# mykeyboard.net
KiCad netlist of a schematic drawn in EasyEDA Pro
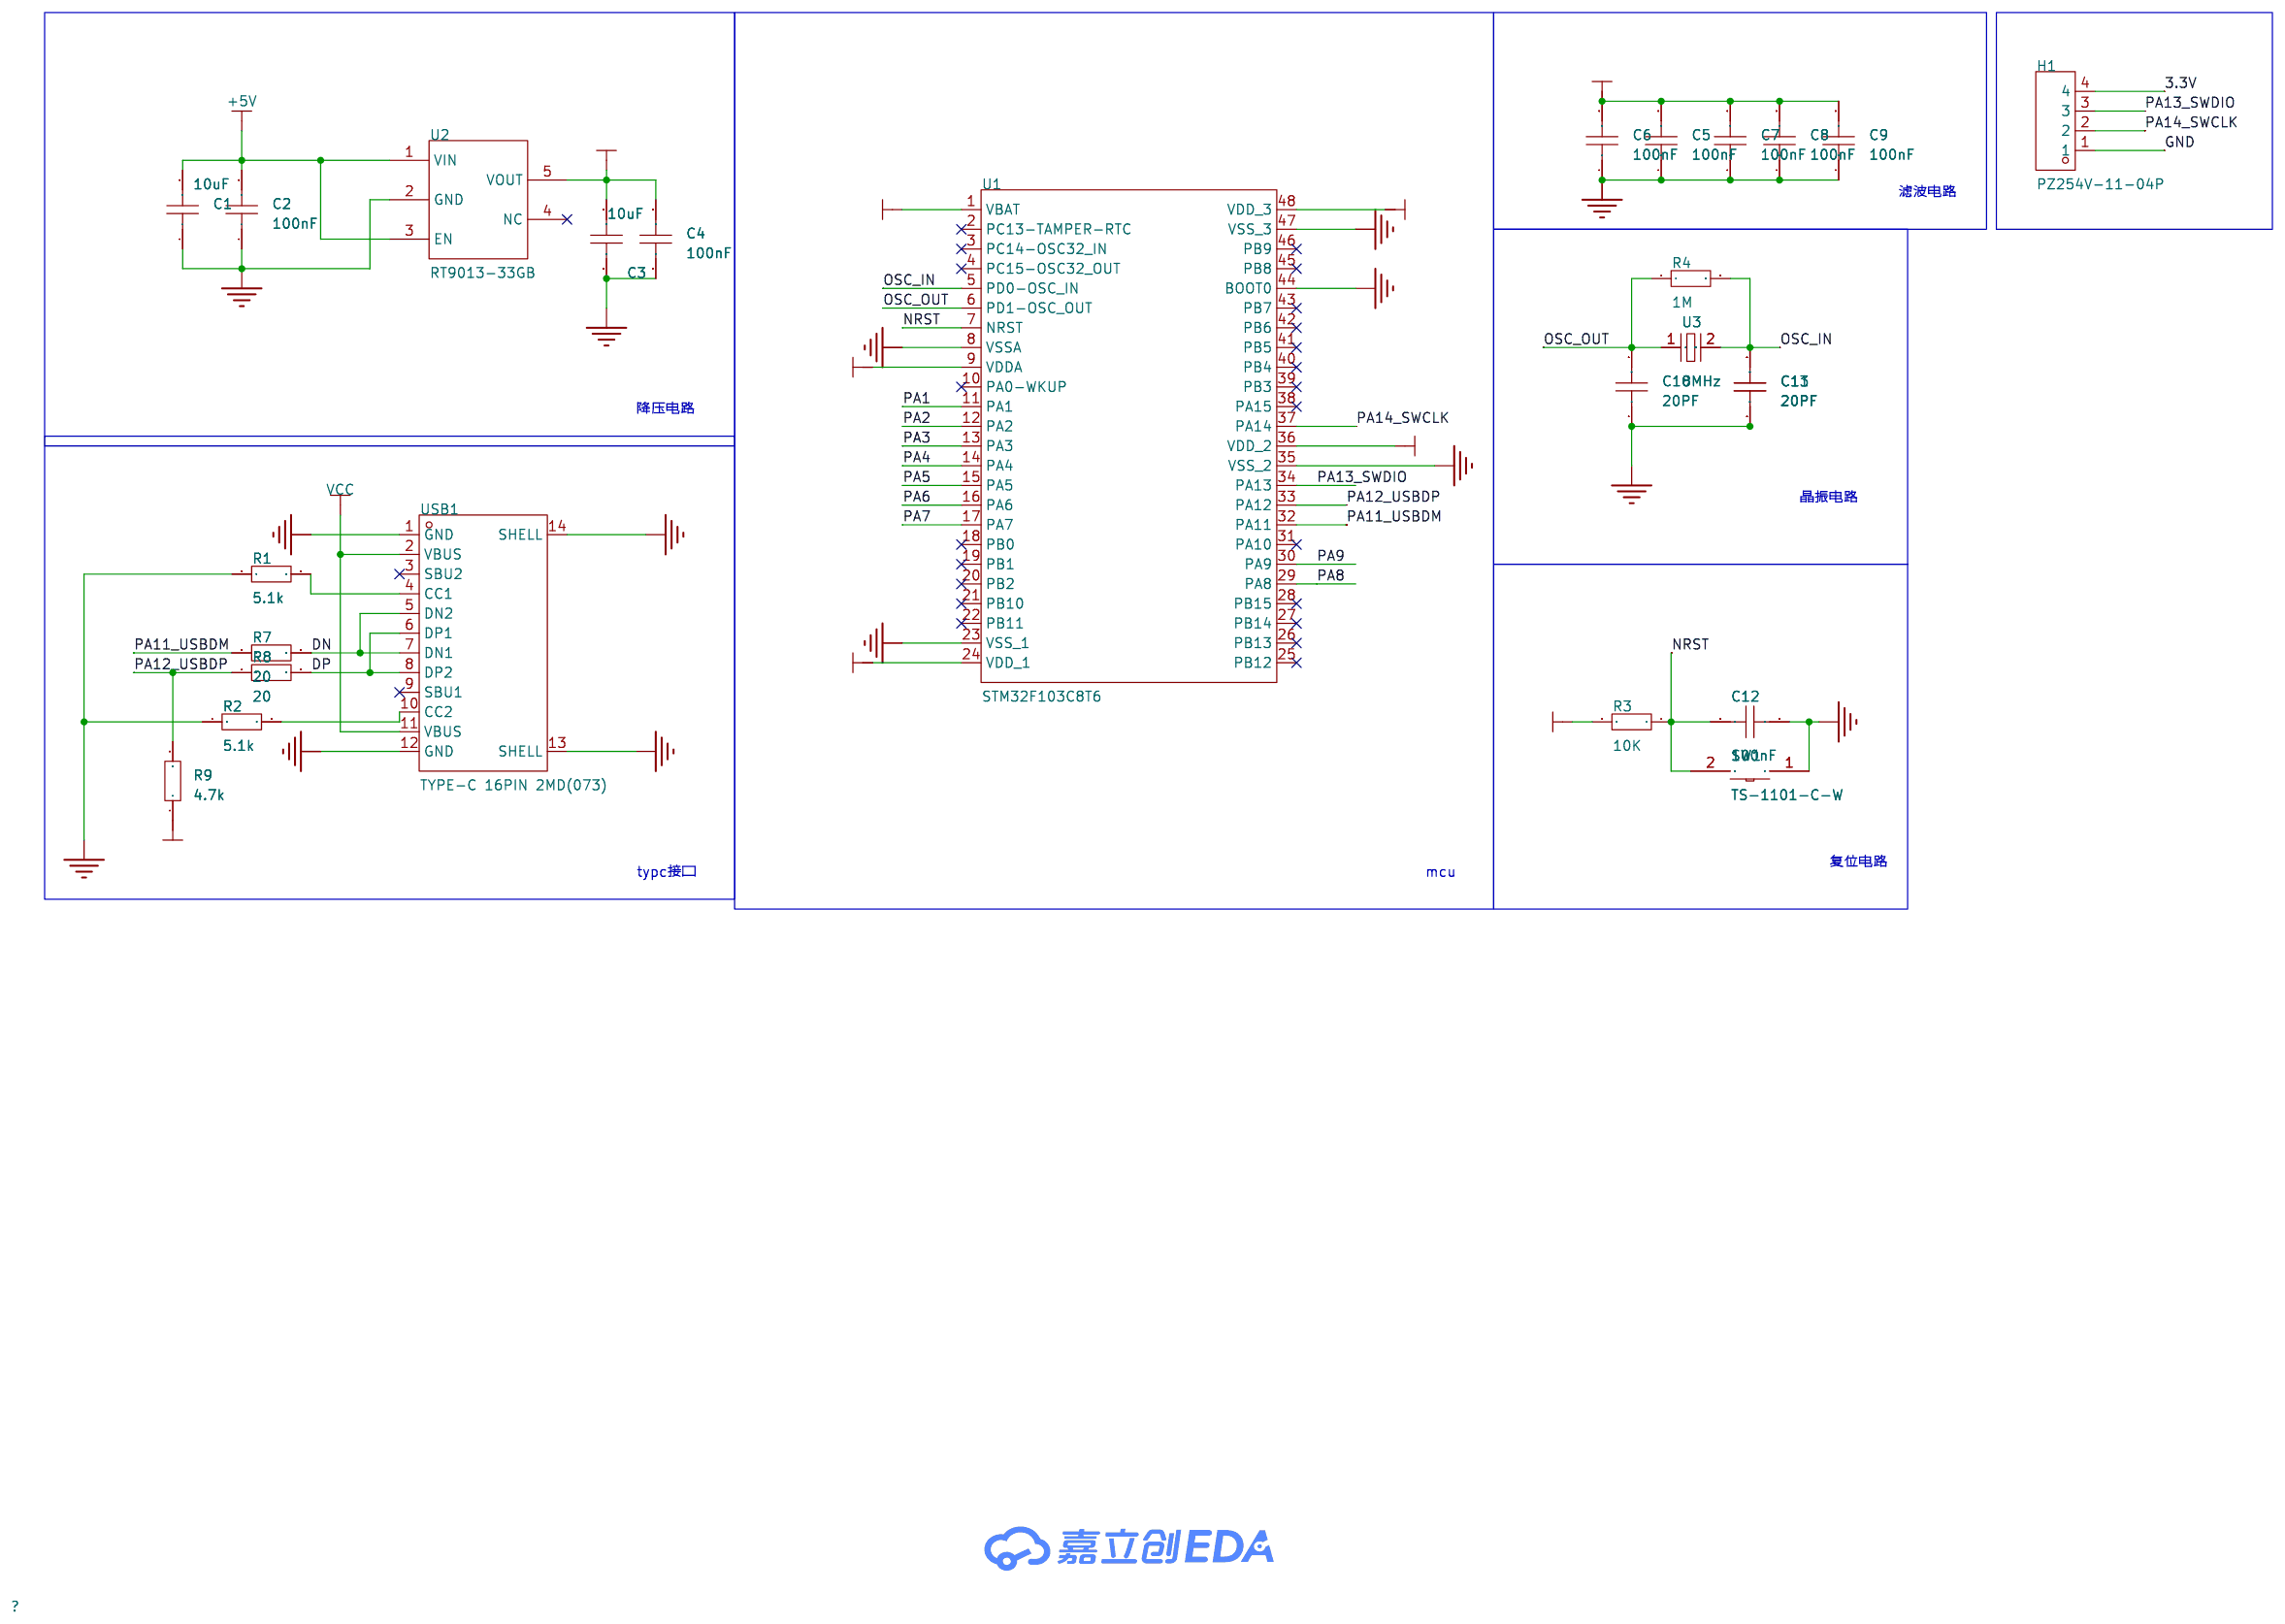
[diagram p0: P1]
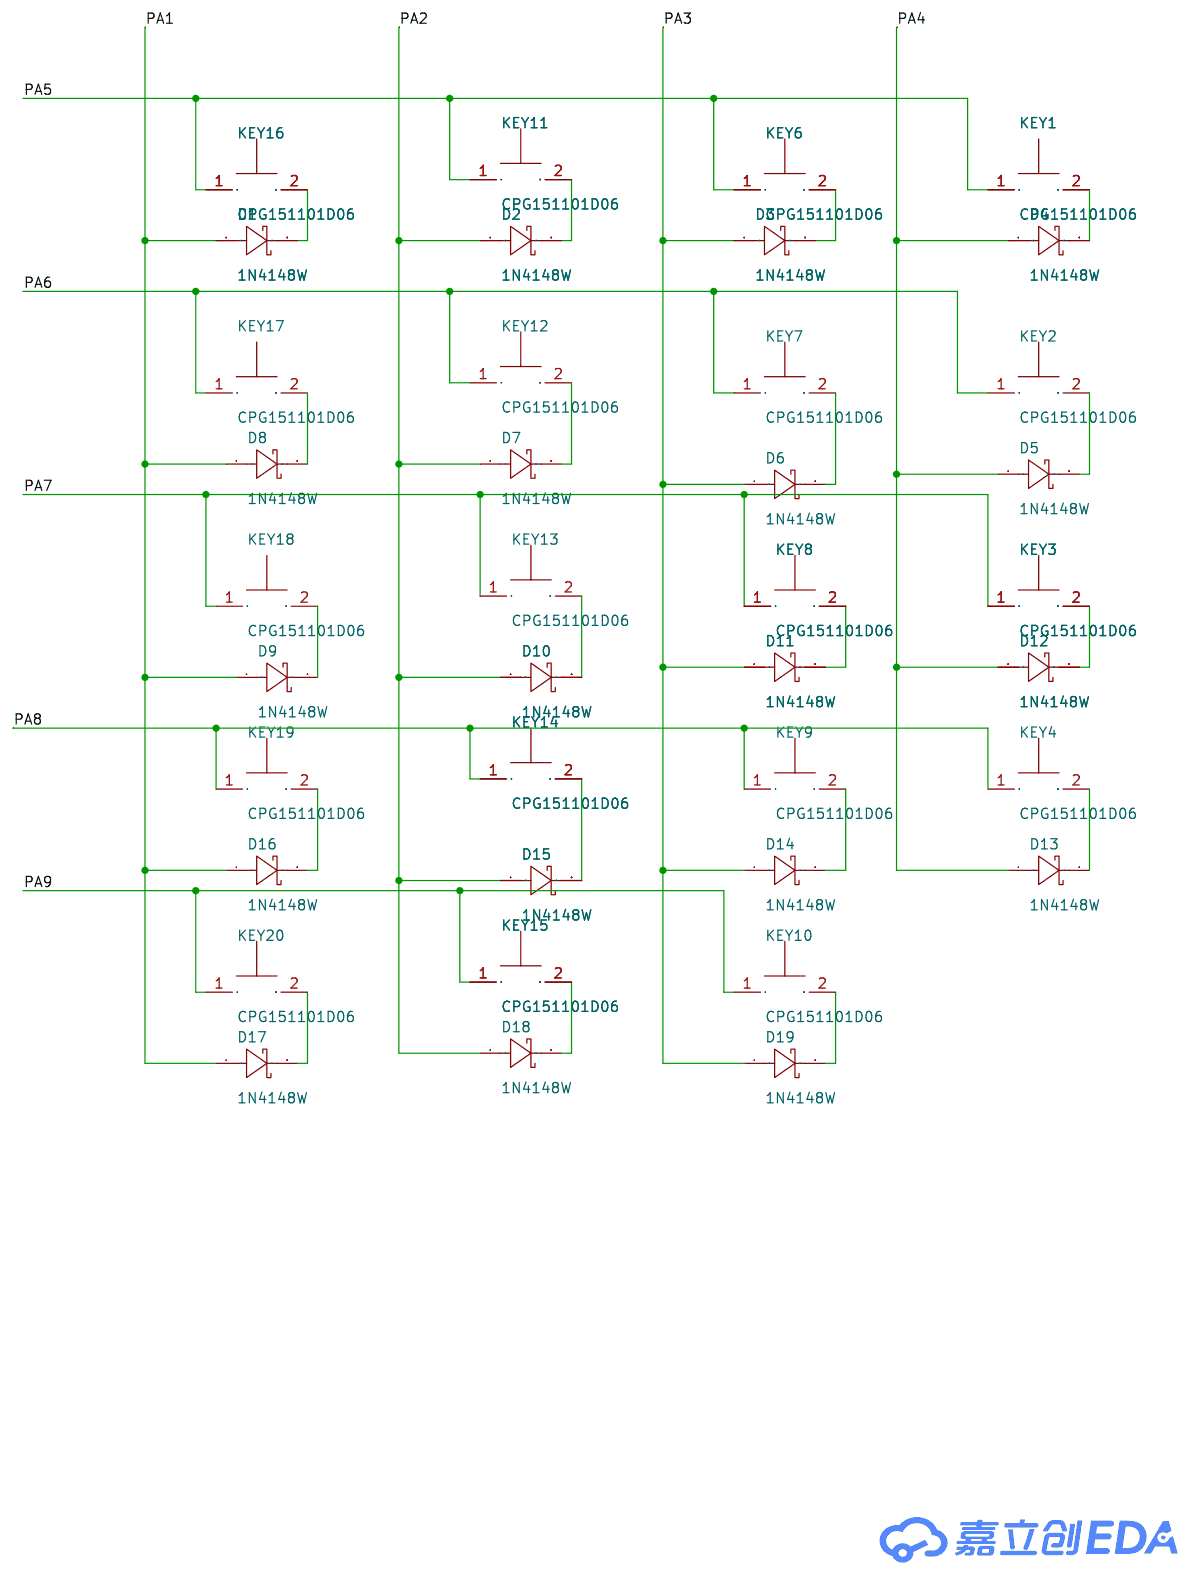
[diagram p1: P2]

(export (version "E")
  (design (tool "Eeschema 10.0.6"))
  (components
    (comp (ref "C1")
      (value "10uF")
      (footprint "easyedapro:C0603")
      (libsource (lib "easyedapro") (part "Capacitance"))
    )
    (comp (ref "C2")
      (value "100nF")
      (footprint "easyedapro:C0603")
      (libsource (lib "easyedapro") (part "Capacitance"))
    )
    (comp (ref "C3")
      (value "10uF")
      (footprint "easyedapro:C0603")
      (libsource (lib "easyedapro") (part "Capacitance"))
    )
    (comp (ref "C4")
      (value "100nF")
      (footprint "easyedapro:C0603")
      (libsource (lib "easyedapro") (part "Capacitance"))
    )
    (comp (ref "C5")
      (value "100nF")
      (footprint "easyedapro:C0603")
      (libsource (lib "easyedapro") (part "Capacitance"))
    )
    (comp (ref "C6")
      (value "100nF")
      (footprint "easyedapro:C0603")
      (libsource (lib "easyedapro") (part "Capacitance"))
    )
    (comp (ref "C7")
      (value "100nF")
      (footprint "easyedapro:C0603")
      (libsource (lib "easyedapro") (part "Capacitance"))
    )
    (comp (ref "C8")
      (value "100nF")
      (footprint "easyedapro:C0603")
      (libsource (lib "easyedapro") (part "Capacitance"))
    )
    (comp (ref "C9")
      (value "100nF")
      (footprint "easyedapro:C0603")
      (libsource (lib "easyedapro") (part "Capacitance"))
    )
    (comp (ref "C10")
      (value "20PF")
      (footprint "easyedapro:C0603")
      (libsource (lib "easyedapro") (part "Capacitance"))
    )
    (comp (ref "C11")
      (value "20PF")
      (footprint "easyedapro:C0603")
      (libsource (lib "easyedapro") (part "Capacitance"))
    )
    (comp (ref "C12")
      (value "100nF")
      (footprint "easyedapro:C0603")
      (libsource (lib "easyedapro") (part "Capacitance"))
    )
    (comp (ref "C13")
      (value "20PF")
      (footprint "easyedapro:C0603")
      (libsource (lib "easyedapro") (part "Capacitance"))
    )
    (comp (ref "H1")
      (value "PZ254V-11-04P")
      (footprint "easyedapro:HDR-TH_4P-P2.54-V-M")
      (fields (field (name "Manufacturer") "XFCN(兴飞)"))
      (libsource (lib "easyedapro") (part "PZ254V-11-04P_C2691448"))
    )
    (comp (ref "R1") (value "5.1k") (footprint "easyedapro:R0603") (libsource (lib "easyedapro") (part "电阻")))
    (comp (ref "R2") (value "5.1k") (footprint "easyedapro:R0603") (libsource (lib "easyedapro") (part "电阻")))
    (comp (ref "R3") (value "10K") (footprint "easyedapro:R0603") (libsource (lib "easyedapro") (part "电阻")))
    (comp (ref "R4") (value "1M") (footprint "easyedapro:R0603") (libsource (lib "easyedapro") (part "电阻")))
    (comp (ref "R7") (value "20") (footprint "easyedapro:R0603") (libsource (lib "easyedapro") (part "电阻")))
    (comp (ref "R8") (value "20") (footprint "easyedapro:R0603") (libsource (lib "easyedapro") (part "电阻")))
    (comp (ref "R9") (value "4.7k") (footprint "easyedapro:R0603") (libsource (lib "easyedapro") (part "电阻")))
    (comp (ref "SW1")
      (value "TS-1101-C-W")
      (footprint "easyedapro:SW-SMD_L6.0-W3.3-LS8.0")
      (fields (field (name "Manufacturer") "XKB Connectivity(中国星坤)"))
      (libsource (lib "easyedapro") (part "TS-1101-C-W"))
    )
    (comp (ref "U1")
      (value "STM32F103C8T6")
      (footprint "easyedapro:LQFP-48_L7.0-W7.0-P0.50-LS9.0-BL")
      (description "CPU内核:ARM-M3;CPU最大主频:72MHz;应用领域:-;")
      (fields (field (name "Manufacturer") "ST(意法半导体)"))
      (libsource (lib "easyedapro") (part "STM32F103C8T6"))
    )
    (comp (ref "U2")
      (value "RT9013-33GB")
      (footprint "easyedapro:SOT-23-5_L3.0-W1.7-P0.95-LS2.8-BL")
      (description "输出类型:固定;工作电压:5.5V;输出电压:3.3V;输出电流:500mA;电源纹波抑制比(PSRR):50dB@(10kHz);输出极性:正极;")
      (fields (field (name "Manufacturer") "RICHTEK(立锜)"))
      (libsource (lib "easyedapro") (part "RT9013-33GB"))
    )
    (comp (ref "U3")
      (value "8MHz")
      (footprint "easyedapro:HC-49S_L7.0-W4.0")
      (description "频率:8MHz;常温频差:±20ppm;负载电容:20pF;频率稳定度:±30ppm;")
      (fields (field (name "Manufacturer Part") "8M 20PF 20PPM") (field (name "Manufacturer") "SOSET(索斯特)"))
      (libsource (lib "easyedapro") (part "8M 20PF 20PPM"))
    )
    (comp (ref "USB1")
      (value "TYPE-C 16PIN 2MD(073)")
      (footprint "easyedapro:USB-C-SMD_TYPE-C-6PIN-2MD-073")
      (description "连接器类型:Type-C;协议标准:-;公母:母;安装方式:卧贴;触点数量:16P;端口数量:1;额定电流 - 电源:3A;工作温度:-25°C~+85°C;")
      (fields (field (name "Manufacturer") "SHOU HAN(首韩)"))
      (libsource (lib "easyedapro") (part "TYPE-C 16PIN 2MD(073)"))
    )
    (comp (ref "D1")
      (value "1N4148W")
      (footprint "easyedapro:SOD-123_L2.7-W1.6-LS3.7-FD")
      (description "二极管配置:独立式;正向压降(Vf):1.25V@150mA;直流反向耐压(Vr):100V;整流电流:150mA;反向恢复时间(Trr):4ns;")
      (fields (field (name "Manufacturer") "R+O(宏嘉诚)"))
      (libsource (lib "easyedapro") (part "1N4148W_C7420318"))
    )
    (comp (ref "D2")
      (value "1N4148W")
      (footprint "easyedapro:SOD-123_L2.7-W1.6-LS3.7-FD")
      (description "二极管配置:独立式;正向压降(Vf):1.25V@150mA;直流反向耐压(Vr):100V;整流电流:150mA;反向恢复时间(Trr):4ns;")
      (fields (field (name "Manufacturer") "R+O(宏嘉诚)"))
      (libsource (lib "easyedapro") (part "1N4148W_C7420318"))
    )
    (comp (ref "D3")
      (value "1N4148W")
      (footprint "easyedapro:SOD-123_L2.7-W1.6-LS3.7-FD")
      (description "二极管配置:独立式;正向压降(Vf):1.25V@150mA;直流反向耐压(Vr):100V;整流电流:150mA;反向恢复时间(Trr):4ns;")
      (fields (field (name "Manufacturer") "R+O(宏嘉诚)"))
      (libsource (lib "easyedapro") (part "1N4148W_C7420318"))
    )
    (comp (ref "D4")
      (value "1N4148W")
      (footprint "easyedapro:SOD-123_L2.7-W1.6-LS3.7-FD")
      (description "二极管配置:独立式;正向压降(Vf):1.25V@150mA;直流反向耐压(Vr):100V;整流电流:150mA;反向恢复时间(Trr):4ns;")
      (fields (field (name "Manufacturer") "R+O(宏嘉诚)"))
      (libsource (lib "easyedapro") (part "1N4148W_C7420318"))
    )
    (comp (ref "D5")
      (value "1N4148W")
      (footprint "easyedapro:SOD-123_L2.7-W1.6-LS3.7-FD")
      (description "二极管配置:独立式;正向压降(Vf):1.25V@150mA;直流反向耐压(Vr):100V;整流电流:150mA;反向恢复时间(Trr):4ns;")
      (fields (field (name "Manufacturer") "R+O(宏嘉诚)"))
      (libsource (lib "easyedapro") (part "1N4148W_C7420318"))
    )
    (comp (ref "D6")
      (value "1N4148W")
      (footprint "easyedapro:SOD-123_L2.7-W1.6-LS3.7-FD")
      (description "二极管配置:独立式;正向压降(Vf):1.25V@150mA;直流反向耐压(Vr):100V;整流电流:150mA;反向恢复时间(Trr):4ns;")
      (fields (field (name "Manufacturer") "R+O(宏嘉诚)"))
      (libsource (lib "easyedapro") (part "1N4148W_C7420318"))
    )
    (comp (ref "D7")
      (value "1N4148W")
      (footprint "easyedapro:SOD-123_L2.7-W1.6-LS3.7-FD")
      (description "二极管配置:独立式;正向压降(Vf):1.25V@150mA;直流反向耐压(Vr):100V;整流电流:150mA;反向恢复时间(Trr):4ns;")
      (fields (field (name "Manufacturer") "R+O(宏嘉诚)"))
      (libsource (lib "easyedapro") (part "1N4148W_C7420318"))
    )
    (comp (ref "D8")
      (value "1N4148W")
      (footprint "easyedapro:SOD-123_L2.7-W1.6-LS3.7-FD")
      (description "二极管配置:独立式;正向压降(Vf):1.25V@150mA;直流反向耐压(Vr):100V;整流电流:150mA;反向恢复时间(Trr):4ns;")
      (fields (field (name "Manufacturer") "R+O(宏嘉诚)"))
      (libsource (lib "easyedapro") (part "1N4148W_C7420318"))
    )
    (comp (ref "D9")
      (value "1N4148W")
      (footprint "easyedapro:SOD-123_L2.7-W1.6-LS3.7-FD")
      (description "二极管配置:独立式;正向压降(Vf):1.25V@150mA;直流反向耐压(Vr):100V;整流电流:150mA;反向恢复时间(Trr):4ns;")
      (fields (field (name "Manufacturer") "R+O(宏嘉诚)"))
      (libsource (lib "easyedapro") (part "1N4148W_C7420318"))
    )
    (comp (ref "D10")
      (value "1N4148W")
      (footprint "easyedapro:SOD-123_L2.7-W1.6-LS3.7-FD")
      (description "二极管配置:独立式;正向压降(Vf):1.25V@150mA;直流反向耐压(Vr):100V;整流电流:150mA;反向恢复时间(Trr):4ns;")
      (fields (field (name "Manufacturer") "R+O(宏嘉诚)"))
      (libsource (lib "easyedapro") (part "1N4148W_C7420318"))
    )
    (comp (ref "D11")
      (value "1N4148W")
      (footprint "easyedapro:SOD-123_L2.7-W1.6-LS3.7-FD")
      (description "二极管配置:独立式;正向压降(Vf):1.25V@150mA;直流反向耐压(Vr):100V;整流电流:150mA;反向恢复时间(Trr):4ns;")
      (fields (field (name "Manufacturer") "R+O(宏嘉诚)"))
      (libsource (lib "easyedapro") (part "1N4148W_C7420318"))
    )
    (comp (ref "D12")
      (value "1N4148W")
      (footprint "easyedapro:SOD-123_L2.7-W1.6-LS3.7-FD")
      (description "二极管配置:独立式;正向压降(Vf):1.25V@150mA;直流反向耐压(Vr):100V;整流电流:150mA;反向恢复时间(Trr):4ns;")
      (fields (field (name "Manufacturer") "R+O(宏嘉诚)"))
      (libsource (lib "easyedapro") (part "1N4148W_C7420318"))
    )
    (comp (ref "D13")
      (value "1N4148W")
      (footprint "easyedapro:SOD-123_L2.7-W1.6-LS3.7-FD")
      (description "二极管配置:独立式;正向压降(Vf):1.25V@150mA;直流反向耐压(Vr):100V;整流电流:150mA;反向恢复时间(Trr):4ns;")
      (fields (field (name "Manufacturer") "R+O(宏嘉诚)"))
      (libsource (lib "easyedapro") (part "1N4148W_C7420318"))
    )
    (comp (ref "D14")
      (value "1N4148W")
      (footprint "easyedapro:SOD-123_L2.7-W1.6-LS3.7-FD")
      (description "二极管配置:独立式;正向压降(Vf):1.25V@150mA;直流反向耐压(Vr):100V;整流电流:150mA;反向恢复时间(Trr):4ns;")
      (fields (field (name "Manufacturer") "R+O(宏嘉诚)"))
      (libsource (lib "easyedapro") (part "1N4148W_C7420318"))
    )
    (comp (ref "D15")
      (value "1N4148W")
      (footprint "easyedapro:SOD-123_L2.7-W1.6-LS3.7-FD")
      (description "二极管配置:独立式;正向压降(Vf):1.25V@150mA;直流反向耐压(Vr):100V;整流电流:150mA;反向恢复时间(Trr):4ns;")
      (fields (field (name "Manufacturer") "R+O(宏嘉诚)"))
      (libsource (lib "easyedapro") (part "1N4148W_C7420318"))
    )
    (comp (ref "D16")
      (value "1N4148W")
      (footprint "easyedapro:SOD-123_L2.7-W1.6-LS3.7-FD")
      (description "二极管配置:独立式;正向压降(Vf):1.25V@150mA;直流反向耐压(Vr):100V;整流电流:150mA;反向恢复时间(Trr):4ns;")
      (fields (field (name "Manufacturer") "R+O(宏嘉诚)"))
      (libsource (lib "easyedapro") (part "1N4148W_C7420318"))
    )
    (comp (ref "D17")
      (value "1N4148W")
      (footprint "easyedapro:SOD-123_L2.7-W1.6-LS3.7-FD")
      (description "二极管配置:独立式;正向压降(Vf):1.25V@150mA;直流反向耐压(Vr):100V;整流电流:150mA;反向恢复时间(Trr):4ns;")
      (fields (field (name "Manufacturer") "R+O(宏嘉诚)"))
      (libsource (lib "easyedapro") (part "1N4148W_C7420318"))
    )
    (comp (ref "D18")
      (value "1N4148W")
      (footprint "easyedapro:SOD-123_L2.7-W1.6-LS3.7-FD")
      (description "二极管配置:独立式;正向压降(Vf):1.25V@150mA;直流反向耐压(Vr):100V;整流电流:150mA;反向恢复时间(Trr):4ns;")
      (fields (field (name "Manufacturer") "R+O(宏嘉诚)"))
      (libsource (lib "easyedapro") (part "1N4148W_C7420318"))
    )
    (comp (ref "D19")
      (value "1N4148W")
      (footprint "easyedapro:SOD-123_L2.7-W1.6-LS3.7-FD")
      (description "二极管配置:独立式;正向压降(Vf):1.25V@150mA;直流反向耐压(Vr):100V;整流电流:150mA;反向恢复时间(Trr):4ns;")
      (fields (field (name "Manufacturer") "R+O(宏嘉诚)"))
      (libsource (lib "easyedapro") (part "1N4148W_C7420318"))
    )
    (comp (ref "KEY1")
      (value "CPG151101D06")
      (footprint "easyedapro:KEY-TH_CPG151101D06")
      (description "机械键盘开关MX茶轴 段落手感")
      (fields (field (name "Manufacturer") "HanElectricity(瀚源)"))
      (libsource (lib "easyedapro") (part "CPG151101D06"))
    )
    (comp (ref "KEY2")
      (value "CPG151101D06")
      (footprint "easyedapro:KEY-TH_CPG151101D06")
      (description "机械键盘开关MX茶轴 段落手感")
      (fields (field (name "Manufacturer") "HanElectricity(瀚源)"))
      (libsource (lib "easyedapro") (part "CPG151101D06"))
    )
    (comp (ref "KEY3")
      (value "CPG151101D06")
      (footprint "easyedapro:KEY-TH_CPG151101D06")
      (description "机械键盘开关MX茶轴 段落手感")
      (fields (field (name "Manufacturer") "HanElectricity(瀚源)"))
      (libsource (lib "easyedapro") (part "CPG151101D06"))
    )
    (comp (ref "KEY4")
      (value "CPG151101D06")
      (footprint "easyedapro:KEY-TH_CPG151101D06")
      (description "机械键盘开关MX茶轴 段落手感")
      (fields (field (name "Manufacturer") "HanElectricity(瀚源)"))
      (libsource (lib "easyedapro") (part "CPG151101D06"))
    )
    (comp (ref "KEY6")
      (value "CPG151101D06")
      (footprint "easyedapro:KEY-TH_CPG151101D06")
      (description "机械键盘开关MX茶轴 段落手感")
      (fields (field (name "Manufacturer") "HanElectricity(瀚源)"))
      (libsource (lib "easyedapro") (part "CPG151101D06"))
    )
    (comp (ref "KEY7")
      (value "CPG151101D06")
      (footprint "easyedapro:KEY-TH_CPG151101D06")
      (description "机械键盘开关MX茶轴 段落手感")
      (fields (field (name "Manufacturer") "HanElectricity(瀚源)"))
      (libsource (lib "easyedapro") (part "CPG151101D06"))
    )
    (comp (ref "KEY8")
      (value "CPG151101D06")
      (footprint "easyedapro:KEY-TH_CPG151101D06")
      (description "机械键盘开关MX茶轴 段落手感")
      (fields (field (name "Manufacturer") "HanElectricity(瀚源)"))
      (libsource (lib "easyedapro") (part "CPG151101D06"))
    )
    (comp (ref "KEY9")
      (value "CPG151101D06")
      (footprint "easyedapro:KEY-TH_CPG151101D06")
      (description "机械键盘开关MX茶轴 段落手感")
      (fields (field (name "Manufacturer") "HanElectricity(瀚源)"))
      (libsource (lib "easyedapro") (part "CPG151101D06"))
    )
    (comp (ref "KEY10")
      (value "CPG151101D06")
      (footprint "easyedapro:KEY-TH_CPG151101D06")
      (description "机械键盘开关MX茶轴 段落手感")
      (fields (field (name "Manufacturer") "HanElectricity(瀚源)"))
      (libsource (lib "easyedapro") (part "CPG151101D06"))
    )
    (comp (ref "KEY11")
      (value "CPG151101D06")
      (footprint "easyedapro:KEY-TH_CPG151101D06")
      (description "机械键盘开关MX茶轴 段落手感")
      (fields (field (name "Manufacturer") "HanElectricity(瀚源)"))
      (libsource (lib "easyedapro") (part "CPG151101D06"))
    )
    (comp (ref "KEY12")
      (value "CPG151101D06")
      (footprint "easyedapro:KEY-TH_CPG151101D06")
      (description "机械键盘开关MX茶轴 段落手感")
      (fields (field (name "Manufacturer") "HanElectricity(瀚源)"))
      (libsource (lib "easyedapro") (part "CPG151101D06"))
    )
    (comp (ref "KEY13")
      (value "CPG151101D06")
      (footprint "easyedapro:KEY-TH_CPG151101D06")
      (description "机械键盘开关MX茶轴 段落手感")
      (fields (field (name "Manufacturer") "HanElectricity(瀚源)"))
      (libsource (lib "easyedapro") (part "CPG151101D06"))
    )
    (comp (ref "KEY14")
      (value "CPG151101D06")
      (footprint "easyedapro:KEY-TH_CPG151101D06")
      (description "机械键盘开关MX茶轴 段落手感")
      (fields (field (name "Manufacturer") "HanElectricity(瀚源)"))
      (libsource (lib "easyedapro") (part "CPG151101D06"))
    )
    (comp (ref "KEY15")
      (value "CPG151101D06")
      (footprint "easyedapro:KEY-TH_CPG151101D06")
      (description "机械键盘开关MX茶轴 段落手感")
      (fields (field (name "Manufacturer") "HanElectricity(瀚源)"))
      (libsource (lib "easyedapro") (part "CPG151101D06"))
    )
    (comp (ref "KEY16")
      (value "CPG151101D06")
      (footprint "easyedapro:KEY-TH_CPG151101D06")
      (description "机械键盘开关MX茶轴 段落手感")
      (fields (field (name "Manufacturer") "HanElectricity(瀚源)"))
      (libsource (lib "easyedapro") (part "CPG151101D06"))
    )
    (comp (ref "KEY17")
      (value "CPG151101D06")
      (footprint "easyedapro:KEY-TH_CPG151101D06")
      (description "机械键盘开关MX茶轴 段落手感")
      (fields (field (name "Manufacturer") "HanElectricity(瀚源)"))
      (libsource (lib "easyedapro") (part "CPG151101D06"))
    )
    (comp (ref "KEY18")
      (value "CPG151101D06")
      (footprint "easyedapro:KEY-TH_CPG151101D06")
      (description "机械键盘开关MX茶轴 段落手感")
      (fields (field (name "Manufacturer") "HanElectricity(瀚源)"))
      (libsource (lib "easyedapro") (part "CPG151101D06"))
    )
    (comp (ref "KEY19")
      (value "CPG151101D06")
      (footprint "easyedapro:KEY-TH_CPG151101D06")
      (description "机械键盘开关MX茶轴 段落手感")
      (fields (field (name "Manufacturer") "HanElectricity(瀚源)"))
      (libsource (lib "easyedapro") (part "CPG151101D06"))
    )
    (comp (ref "KEY20")
      (value "CPG151101D06")
      (footprint "easyedapro:KEY-TH_CPG151101D06")
      (description "机械键盘开关MX茶轴 段落手感")
      (fields (field (name "Manufacturer") "HanElectricity(瀚源)"))
      (libsource (lib "easyedapro") (part "CPG151101D06"))
    )
  )
  (nets
    (net (code "1") (name "+5V") (class "Default")
      (node (ref "C1") (pin "2") (pinfunction "2_2") (pintype "input"))
      (node (ref "C2") (pin "2") (pinfunction "2_2") (pintype "input"))
      (node (ref "U2") (pin "1") (pinfunction "VIN_1") (pintype "unspecified"))
      (node (ref "U2") (pin "3") (pinfunction "EN_3") (pintype "unspecified"))
    )
    (net (code "2") (name "3.3V") (class "Default")
      (node (ref "C3") (pin "2") (pinfunction "2_2") (pintype "input"))
      (node (ref "C4") (pin "2") (pinfunction "2_2") (pintype "input"))
      (node (ref "C5") (pin "2") (pinfunction "2_2") (pintype "input"))
      (node (ref "C6") (pin "2") (pinfunction "2_2") (pintype "input"))
      (node (ref "C7") (pin "2") (pinfunction "2_2") (pintype "input"))
      (node (ref "C8") (pin "2") (pinfunction "2_2") (pintype "input"))
      (node (ref "C9") (pin "2") (pinfunction "2_2") (pintype "input"))
      (node (ref "H1") (pin "4") (pinfunction "4_4") (pintype "unspecified"))
      (node (ref "R3") (pin "2") (pinfunction "2_2") (pintype "input"))
      (node (ref "R9") (pin "1") (pinfunction "1_1") (pintype "input"))
      (node (ref "U1") (pin "1") (pinfunction "VBAT_1") (pintype "unspecified"))
      (node (ref "U1") (pin "24") (pinfunction "VDD_1_24") (pintype "unspecified"))
      (node (ref "U1") (pin "36") (pinfunction "VDD_2_36") (pintype "unspecified"))
      (node (ref "U1") (pin "48") (pinfunction "VDD_3_48") (pintype "unspecified"))
      (node (ref "U1") (pin "9") (pinfunction "VDDA_9") (pintype "unspecified"))
      (node (ref "U2") (pin "5") (pinfunction "VOUT_5") (pintype "unspecified"))
    )
    (net (code "3") (name "DN") (class "Default")
      (node (ref "R7") (pin "2") (pinfunction "2_2") (pintype "input"))
      (node (ref "USB1") (pin "5") (pinfunction "DN2_5") (pintype "unspecified"))
      (node (ref "USB1") (pin "7") (pinfunction "DN1_7") (pintype "unspecified"))
    )
    (net (code "4") (name "DP") (class "Default")
      (node (ref "R8") (pin "2") (pinfunction "2_2") (pintype "input"))
      (node (ref "USB1") (pin "6") (pinfunction "DP1_6") (pintype "unspecified"))
      (node (ref "USB1") (pin "8") (pinfunction "DP2_8") (pintype "unspecified"))
    )
    (net (code "5") (name "GND") (class "Default")
      (node (ref "C1") (pin "1") (pinfunction "1_1") (pintype "input"))
      (node (ref "C10") (pin "1") (pinfunction "1_1") (pintype "input"))
      (node (ref "C11") (pin "1") (pinfunction "1_1") (pintype "input"))
      (node (ref "C12") (pin "1") (pinfunction "1_1") (pintype "input"))
      (node (ref "C13") (pin "1") (pinfunction "1_1") (pintype "input"))
      (node (ref "C2") (pin "1") (pinfunction "1_1") (pintype "input"))
      (node (ref "C3") (pin "1") (pinfunction "1_1") (pintype "input"))
      (node (ref "C4") (pin "1") (pinfunction "1_1") (pintype "input"))
      (node (ref "C5") (pin "1") (pinfunction "1_1") (pintype "input"))
      (node (ref "C6") (pin "1") (pinfunction "1_1") (pintype "input"))
      (node (ref "C7") (pin "1") (pinfunction "1_1") (pintype "input"))
      (node (ref "C8") (pin "1") (pinfunction "1_1") (pintype "input"))
      (node (ref "C9") (pin "1") (pinfunction "1_1") (pintype "input"))
      (node (ref "H1") (pin "1") (pinfunction "1_1") (pintype "unspecified"))
      (node (ref "R1") (pin "1") (pinfunction "1_1") (pintype "input"))
      (node (ref "R2") (pin "1") (pinfunction "1_1") (pintype "input"))
      (node (ref "SW1") (pin "1") (pinfunction "1_1") (pintype "unspecified"))
      (node (ref "U1") (pin "23") (pinfunction "VSS_1_23") (pintype "unspecified"))
      (node (ref "U1") (pin "35") (pinfunction "VSS_2_35") (pintype "unspecified"))
      (node (ref "U1") (pin "44") (pinfunction "BOOT0_44") (pintype "unspecified"))
      (node (ref "U1") (pin "47") (pinfunction "VSS_3_47") (pintype "unspecified"))
      (node (ref "U1") (pin "8") (pinfunction "VSSA_8") (pintype "unspecified"))
      (node (ref "U2") (pin "2") (pinfunction "GND_2") (pintype "unspecified"))
      (node (ref "USB1") (pin "1") (pinfunction "GND_1") (pintype "unspecified"))
      (node (ref "USB1") (pin "12") (pinfunction "GND_12") (pintype "unspecified"))
      (node (ref "USB1") (pin "13") (pinfunction "SHELL_13") (pintype "unspecified"))
      (node (ref "USB1") (pin "14") (pinfunction "SHELL_14") (pintype "unspecified"))
    )
    (net (code "6") (name "NRST") (class "Default")
      (node (ref "C12") (pin "2") (pinfunction "2_2") (pintype "input"))
      (node (ref "R3") (pin "1") (pinfunction "1_1") (pintype "input"))
      (node (ref "SW1") (pin "2") (pinfunction "2_2") (pintype "unspecified"))
      (node (ref "U1") (pin "7") (pinfunction "NRST_7") (pintype "unspecified"))
    )
    (net (code "7") (name "Net-(D1-K)") (class "Default")
      (node (ref "D1") (pin "2") (pinfunction "K_2") (pintype "unspecified"))
      (node (ref "KEY16") (pin "2") (pinfunction "2_2") (pintype "unspecified"))
    )
    (net (code "8") (name "Net-(D2-K)") (class "Default")
      (node (ref "D2") (pin "2") (pinfunction "K_2") (pintype "unspecified"))
      (node (ref "KEY11") (pin "2") (pinfunction "2_2") (pintype "unspecified"))
    )
    (net (code "9") (name "Net-(D3-K)") (class "Default")
      (node (ref "D3") (pin "2") (pinfunction "K_2") (pintype "unspecified"))
      (node (ref "KEY6") (pin "2") (pinfunction "2_2") (pintype "unspecified"))
    )
    (net (code "10") (name "Net-(D4-K)") (class "Default")
      (node (ref "D4") (pin "2") (pinfunction "K_2") (pintype "unspecified"))
      (node (ref "KEY1") (pin "2") (pinfunction "2_2") (pintype "unspecified"))
    )
    (net (code "11") (name "Net-(D5-K)") (class "Default")
      (node (ref "D5") (pin "2") (pinfunction "K_2") (pintype "unspecified"))
      (node (ref "KEY2") (pin "2") (pinfunction "2_2") (pintype "unspecified"))
    )
    (net (code "12") (name "Net-(D6-K)") (class "Default")
      (node (ref "D6") (pin "2") (pinfunction "K_2") (pintype "unspecified"))
      (node (ref "KEY7") (pin "2") (pinfunction "2_2") (pintype "unspecified"))
    )
    (net (code "13") (name "Net-(D7-K)") (class "Default")
      (node (ref "D7") (pin "2") (pinfunction "K_2") (pintype "unspecified"))
      (node (ref "KEY12") (pin "2") (pinfunction "2_2") (pintype "unspecified"))
    )
    (net (code "14") (name "Net-(D8-K)") (class "Default")
      (node (ref "D8") (pin "2") (pinfunction "K_2") (pintype "unspecified"))
      (node (ref "KEY17") (pin "2") (pinfunction "2_2") (pintype "unspecified"))
    )
    (net (code "15") (name "Net-(D9-K)") (class "Default")
      (node (ref "D9") (pin "2") (pinfunction "K_2") (pintype "unspecified"))
      (node (ref "KEY18") (pin "2") (pinfunction "2_2") (pintype "unspecified"))
    )
    (net (code "16") (name "Net-(D10-K)") (class "Default")
      (node (ref "D10") (pin "2") (pinfunction "K_2") (pintype "unspecified"))
      (node (ref "KEY13") (pin "2") (pinfunction "2_2") (pintype "unspecified"))
    )
    (net (code "17") (name "Net-(D11-K)") (class "Default")
      (node (ref "D11") (pin "2") (pinfunction "K_2") (pintype "unspecified"))
      (node (ref "KEY8") (pin "2") (pinfunction "2_2") (pintype "unspecified"))
    )
    (net (code "18") (name "Net-(D12-K)") (class "Default")
      (node (ref "D12") (pin "2") (pinfunction "K_2") (pintype "unspecified"))
      (node (ref "KEY3") (pin "2") (pinfunction "2_2") (pintype "unspecified"))
    )
    (net (code "19") (name "Net-(D13-K)") (class "Default")
      (node (ref "D13") (pin "2") (pinfunction "K_2") (pintype "unspecified"))
      (node (ref "KEY4") (pin "2") (pinfunction "2_2") (pintype "unspecified"))
    )
    (net (code "20") (name "Net-(D14-K)") (class "Default")
      (node (ref "D14") (pin "2") (pinfunction "K_2") (pintype "unspecified"))
      (node (ref "KEY9") (pin "2") (pinfunction "2_2") (pintype "unspecified"))
    )
    (net (code "21") (name "Net-(D15-K)") (class "Default")
      (node (ref "D15") (pin "2") (pinfunction "K_2") (pintype "unspecified"))
      (node (ref "KEY14") (pin "2") (pinfunction "2_2") (pintype "unspecified"))
    )
    (net (code "22") (name "Net-(D16-K)") (class "Default")
      (node (ref "D16") (pin "2") (pinfunction "K_2") (pintype "unspecified"))
      (node (ref "KEY19") (pin "2") (pinfunction "2_2") (pintype "unspecified"))
    )
    (net (code "23") (name "Net-(D17-K)") (class "Default")
      (node (ref "D17") (pin "2") (pinfunction "K_2") (pintype "unspecified"))
      (node (ref "KEY20") (pin "2") (pinfunction "2_2") (pintype "unspecified"))
    )
    (net (code "24") (name "Net-(D18-K)") (class "Default")
      (node (ref "D18") (pin "2") (pinfunction "K_2") (pintype "unspecified"))
      (node (ref "KEY15") (pin "2") (pinfunction "2_2") (pintype "unspecified"))
    )
    (net (code "25") (name "Net-(D19-K)") (class "Default")
      (node (ref "D19") (pin "2") (pinfunction "K_2") (pintype "unspecified"))
      (node (ref "KEY10") (pin "2") (pinfunction "2_2") (pintype "unspecified"))
    )
    (net (code "26") (name "Net-(USB1-CC1)") (class "Default")
      (node (ref "R1") (pin "2") (pinfunction "2_2") (pintype "input"))
      (node (ref "USB1") (pin "4") (pinfunction "CC1_4") (pintype "unspecified"))
    )
    (net (code "27") (name "Net-(USB1-CC2)") (class "Default")
      (node (ref "R2") (pin "2") (pinfunction "2_2") (pintype "input"))
      (node (ref "USB1") (pin "10") (pinfunction "CC2_10") (pintype "unspecified"))
    )
    (net (code "28") (name "OSC_IN") (class "Default")
      (node (ref "C11") (pin "2") (pinfunction "2_2") (pintype "input"))
      (node (ref "C13") (pin "2") (pinfunction "2_2") (pintype "input"))
      (node (ref "R4") (pin "2") (pinfunction "2_2") (pintype "input"))
      (node (ref "U1") (pin "5") (pinfunction "PD0-OSC_IN_5") (pintype "unspecified"))
      (node (ref "U3") (pin "2") (pinfunction "GND_2") (pintype "input"))
    )
    (net (code "29") (name "OSC_OUT") (class "Default")
      (node (ref "C10") (pin "2") (pinfunction "2_2") (pintype "input"))
      (node (ref "R4") (pin "1") (pinfunction "1_1") (pintype "input"))
      (node (ref "U1") (pin "6") (pinfunction "PD1-OSC_OUT_6") (pintype "unspecified"))
      (node (ref "U3") (pin "1") (pinfunction "1_1") (pintype "input"))
    )
    (net (code "30") (name "PA1") (class "Default")
      (node (ref "D1") (pin "1") (pinfunction "A_1") (pintype "unspecified"))
      (node (ref "D16") (pin "1") (pinfunction "A_1") (pintype "unspecified"))
      (node (ref "D17") (pin "1") (pinfunction "A_1") (pintype "unspecified"))
      (node (ref "D8") (pin "1") (pinfunction "A_1") (pintype "unspecified"))
      (node (ref "D9") (pin "1") (pinfunction "A_1") (pintype "unspecified"))
      (node (ref "U1") (pin "11") (pinfunction "PA1_11") (pintype "unspecified"))
    )
    (net (code "31") (name "PA2") (class "Default")
      (node (ref "D10") (pin "1") (pinfunction "A_1") (pintype "unspecified"))
      (node (ref "D15") (pin "1") (pinfunction "A_1") (pintype "unspecified"))
      (node (ref "D18") (pin "1") (pinfunction "A_1") (pintype "unspecified"))
      (node (ref "D2") (pin "1") (pinfunction "A_1") (pintype "unspecified"))
      (node (ref "D7") (pin "1") (pinfunction "A_1") (pintype "unspecified"))
      (node (ref "U1") (pin "12") (pinfunction "PA2_12") (pintype "unspecified"))
    )
    (net (code "32") (name "PA3") (class "Default")
      (node (ref "D11") (pin "1") (pinfunction "A_1") (pintype "unspecified"))
      (node (ref "D14") (pin "1") (pinfunction "A_1") (pintype "unspecified"))
      (node (ref "D19") (pin "1") (pinfunction "A_1") (pintype "unspecified"))
      (node (ref "D3") (pin "1") (pinfunction "A_1") (pintype "unspecified"))
      (node (ref "D6") (pin "1") (pinfunction "A_1") (pintype "unspecified"))
      (node (ref "U1") (pin "13") (pinfunction "PA3_13") (pintype "unspecified"))
    )
    (net (code "33") (name "PA4") (class "Default")
      (node (ref "D12") (pin "1") (pinfunction "A_1") (pintype "unspecified"))
      (node (ref "D13") (pin "1") (pinfunction "A_1") (pintype "unspecified"))
      (node (ref "D4") (pin "1") (pinfunction "A_1") (pintype "unspecified"))
      (node (ref "D5") (pin "1") (pinfunction "A_1") (pintype "unspecified"))
      (node (ref "U1") (pin "14") (pinfunction "PA4_14") (pintype "unspecified"))
    )
    (net (code "34") (name "PA5") (class "Default")
      (node (ref "KEY1") (pin "1") (pinfunction "1_1") (pintype "unspecified"))
      (node (ref "KEY11") (pin "1") (pinfunction "1_1") (pintype "unspecified"))
      (node (ref "KEY16") (pin "1") (pinfunction "1_1") (pintype "unspecified"))
      (node (ref "KEY6") (pin "1") (pinfunction "1_1") (pintype "unspecified"))
      (node (ref "U1") (pin "15") (pinfunction "PA5_15") (pintype "unspecified"))
    )
    (net (code "35") (name "PA6") (class "Default")
      (node (ref "KEY12") (pin "1") (pinfunction "1_1") (pintype "unspecified"))
      (node (ref "KEY17") (pin "1") (pinfunction "1_1") (pintype "unspecified"))
      (node (ref "KEY2") (pin "1") (pinfunction "1_1") (pintype "unspecified"))
      (node (ref "KEY7") (pin "1") (pinfunction "1_1") (pintype "unspecified"))
      (node (ref "U1") (pin "16") (pinfunction "PA6_16") (pintype "unspecified"))
    )
    (net (code "36") (name "PA7") (class "Default")
      (node (ref "KEY13") (pin "1") (pinfunction "1_1") (pintype "unspecified"))
      (node (ref "KEY18") (pin "1") (pinfunction "1_1") (pintype "unspecified"))
      (node (ref "KEY3") (pin "1") (pinfunction "1_1") (pintype "unspecified"))
      (node (ref "KEY8") (pin "1") (pinfunction "1_1") (pintype "unspecified"))
      (node (ref "U1") (pin "17") (pinfunction "PA7_17") (pintype "unspecified"))
    )
    (net (code "37") (name "PA8") (class "Default")
      (node (ref "KEY14") (pin "1") (pinfunction "1_1") (pintype "unspecified"))
      (node (ref "KEY19") (pin "1") (pinfunction "1_1") (pintype "unspecified"))
      (node (ref "KEY4") (pin "1") (pinfunction "1_1") (pintype "unspecified"))
      (node (ref "KEY9") (pin "1") (pinfunction "1_1") (pintype "unspecified"))
      (node (ref "U1") (pin "29") (pinfunction "PA8_29") (pintype "unspecified"))
    )
    (net (code "38") (name "PA9") (class "Default")
      (node (ref "KEY10") (pin "1") (pinfunction "1_1") (pintype "unspecified"))
      (node (ref "KEY15") (pin "1") (pinfunction "1_1") (pintype "unspecified"))
      (node (ref "KEY20") (pin "1") (pinfunction "1_1") (pintype "unspecified"))
      (node (ref "U1") (pin "30") (pinfunction "PA9_30") (pintype "unspecified"))
    )
    (net (code "39") (name "PA11_USBDM") (class "Default")
      (node (ref "R7") (pin "1") (pinfunction "1_1") (pintype "input"))
      (node (ref "U1") (pin "32") (pinfunction "PA11_32") (pintype "unspecified"))
    )
    (net (code "40") (name "PA12_USBDP") (class "Default")
      (node (ref "R8") (pin "1") (pinfunction "1_1") (pintype "input"))
      (node (ref "R9") (pin "2") (pinfunction "2_2") (pintype "input"))
      (node (ref "U1") (pin "33") (pinfunction "PA12_33") (pintype "unspecified"))
    )
    (net (code "41") (name "PA13_SWDIO") (class "Default")
      (node (ref "H1") (pin "3") (pinfunction "3_3") (pintype "unspecified"))
      (node (ref "U1") (pin "34") (pinfunction "PA13_34") (pintype "unspecified"))
    )
    (net (code "42") (name "PA14_SWCLK") (class "Default")
      (node (ref "H1") (pin "2") (pinfunction "2_2") (pintype "unspecified"))
      (node (ref "U1") (pin "37") (pinfunction "PA14_37") (pintype "unspecified"))
    )
    (net (code "43") (name "VCC") (class "Default")
      (node (ref "USB1") (pin "11") (pinfunction "VBUS_11") (pintype "unspecified"))
      (node (ref "USB1") (pin "2") (pinfunction "VBUS_2") (pintype "unspecified"))
    )
    (net (code "44") (name "unconnected-(U1-PA0-WKUP-Pad10)") (class "Default")
      (node (ref "U1") (pin "10") (pinfunction "PA0-WKUP_10") (pintype "unspecified+no_connect"))
    )
    (net (code "45") (name "unconnected-(U1-PA10-Pad31)") (class "Default")
      (node (ref "U1") (pin "31") (pinfunction "PA10_31") (pintype "unspecified+no_connect"))
    )
    (net (code "46") (name "unconnected-(U1-PA15-Pad38)") (class "Default")
      (node (ref "U1") (pin "38") (pinfunction "PA15_38") (pintype "unspecified+no_connect"))
    )
    (net (code "47") (name "unconnected-(U1-PB0-Pad18)") (class "Default")
      (node (ref "U1") (pin "18") (pinfunction "PB0_18") (pintype "unspecified+no_connect"))
    )
    (net (code "48") (name "unconnected-(U1-PB1-Pad19)") (class "Default")
      (node (ref "U1") (pin "19") (pinfunction "PB1_19") (pintype "unspecified+no_connect"))
    )
    (net (code "49") (name "unconnected-(U1-PB2-Pad20)") (class "Default")
      (node (ref "U1") (pin "20") (pinfunction "PB2_20") (pintype "unspecified+no_connect"))
    )
    (net (code "50") (name "unconnected-(U1-PB3-Pad39)") (class "Default")
      (node (ref "U1") (pin "39") (pinfunction "PB3_39") (pintype "unspecified+no_connect"))
    )
    (net (code "51") (name "unconnected-(U1-PB4-Pad40)") (class "Default")
      (node (ref "U1") (pin "40") (pinfunction "PB4_40") (pintype "unspecified+no_connect"))
    )
    (net (code "52") (name "unconnected-(U1-PB5-Pad41)") (class "Default")
      (node (ref "U1") (pin "41") (pinfunction "PB5_41") (pintype "unspecified+no_connect"))
    )
    (net (code "53") (name "unconnected-(U1-PB6-Pad42)") (class "Default")
      (node (ref "U1") (pin "42") (pinfunction "PB6_42") (pintype "unspecified+no_connect"))
    )
    (net (code "54") (name "unconnected-(U1-PB7-Pad43)") (class "Default")
      (node (ref "U1") (pin "43") (pinfunction "PB7_43") (pintype "unspecified+no_connect"))
    )
    (net (code "55") (name "unconnected-(U1-PB8-Pad45)") (class "Default")
      (node (ref "U1") (pin "45") (pinfunction "PB8_45") (pintype "unspecified+no_connect"))
    )
    (net (code "56") (name "unconnected-(U1-PB9-Pad46)") (class "Default")
      (node (ref "U1") (pin "46") (pinfunction "PB9_46") (pintype "unspecified+no_connect"))
    )
    (net (code "57") (name "unconnected-(U1-PB10-Pad21)") (class "Default")
      (node (ref "U1") (pin "21") (pinfunction "PB10_21") (pintype "unspecified+no_connect"))
    )
    (net (code "58") (name "unconnected-(U1-PB11-Pad22)") (class "Default")
      (node (ref "U1") (pin "22") (pinfunction "PB11_22") (pintype "unspecified+no_connect"))
    )
    (net (code "59") (name "unconnected-(U1-PB12-Pad25)") (class "Default")
      (node (ref "U1") (pin "25") (pinfunction "PB12_25") (pintype "unspecified+no_connect"))
    )
    (net (code "60") (name "unconnected-(U1-PB13-Pad26)") (class "Default")
      (node (ref "U1") (pin "26") (pinfunction "PB13_26") (pintype "unspecified+no_connect"))
    )
    (net (code "61") (name "unconnected-(U1-PB14-Pad27)") (class "Default")
      (node (ref "U1") (pin "27") (pinfunction "PB14_27") (pintype "unspecified+no_connect"))
    )
    (net (code "62") (name "unconnected-(U1-PB15-Pad28)") (class "Default")
      (node (ref "U1") (pin "28") (pinfunction "PB15_28") (pintype "unspecified+no_connect"))
    )
    (net (code "63") (name "unconnected-(U1-PC13-TAMPER-RTC-Pad2)") (class "Default")
      (node (ref "U1") (pin "2") (pinfunction "PC13-TAMPER-RTC_2") (pintype "unspecified+no_connect"))
    )
    (net (code "64") (name "unconnected-(U1-PC14-OSC32_IN-Pad3)") (class "Default")
      (node (ref "U1") (pin "3") (pinfunction "PC14-OSC32_IN_3") (pintype "unspecified+no_connect"))
    )
    (net (code "65") (name "unconnected-(U1-PC15-OSC32_OUT-Pad4)") (class "Default")
      (node (ref "U1") (pin "4") (pinfunction "PC15-OSC32_OUT_4") (pintype "unspecified+no_connect"))
    )
    (net (code "66") (name "unconnected-(U2-NC-Pad4)") (class "Default")
      (node (ref "U2") (pin "4") (pinfunction "NC_4") (pintype "unspecified+no_connect"))
    )
    (net (code "67") (name "unconnected-(USB1-SBU1-Pad9)") (class "Default")
      (node (ref "USB1") (pin "9") (pinfunction "SBU1_9") (pintype "unspecified+no_connect"))
    )
    (net (code "68") (name "unconnected-(USB1-SBU2-Pad3)") (class "Default")
      (node (ref "USB1") (pin "3") (pinfunction "SBU2_3") (pintype "unspecified+no_connect"))
    )
  )
)
